# I2C_Breakout_Block.net
KiCad netlist of a schematic drawn in EAGLE
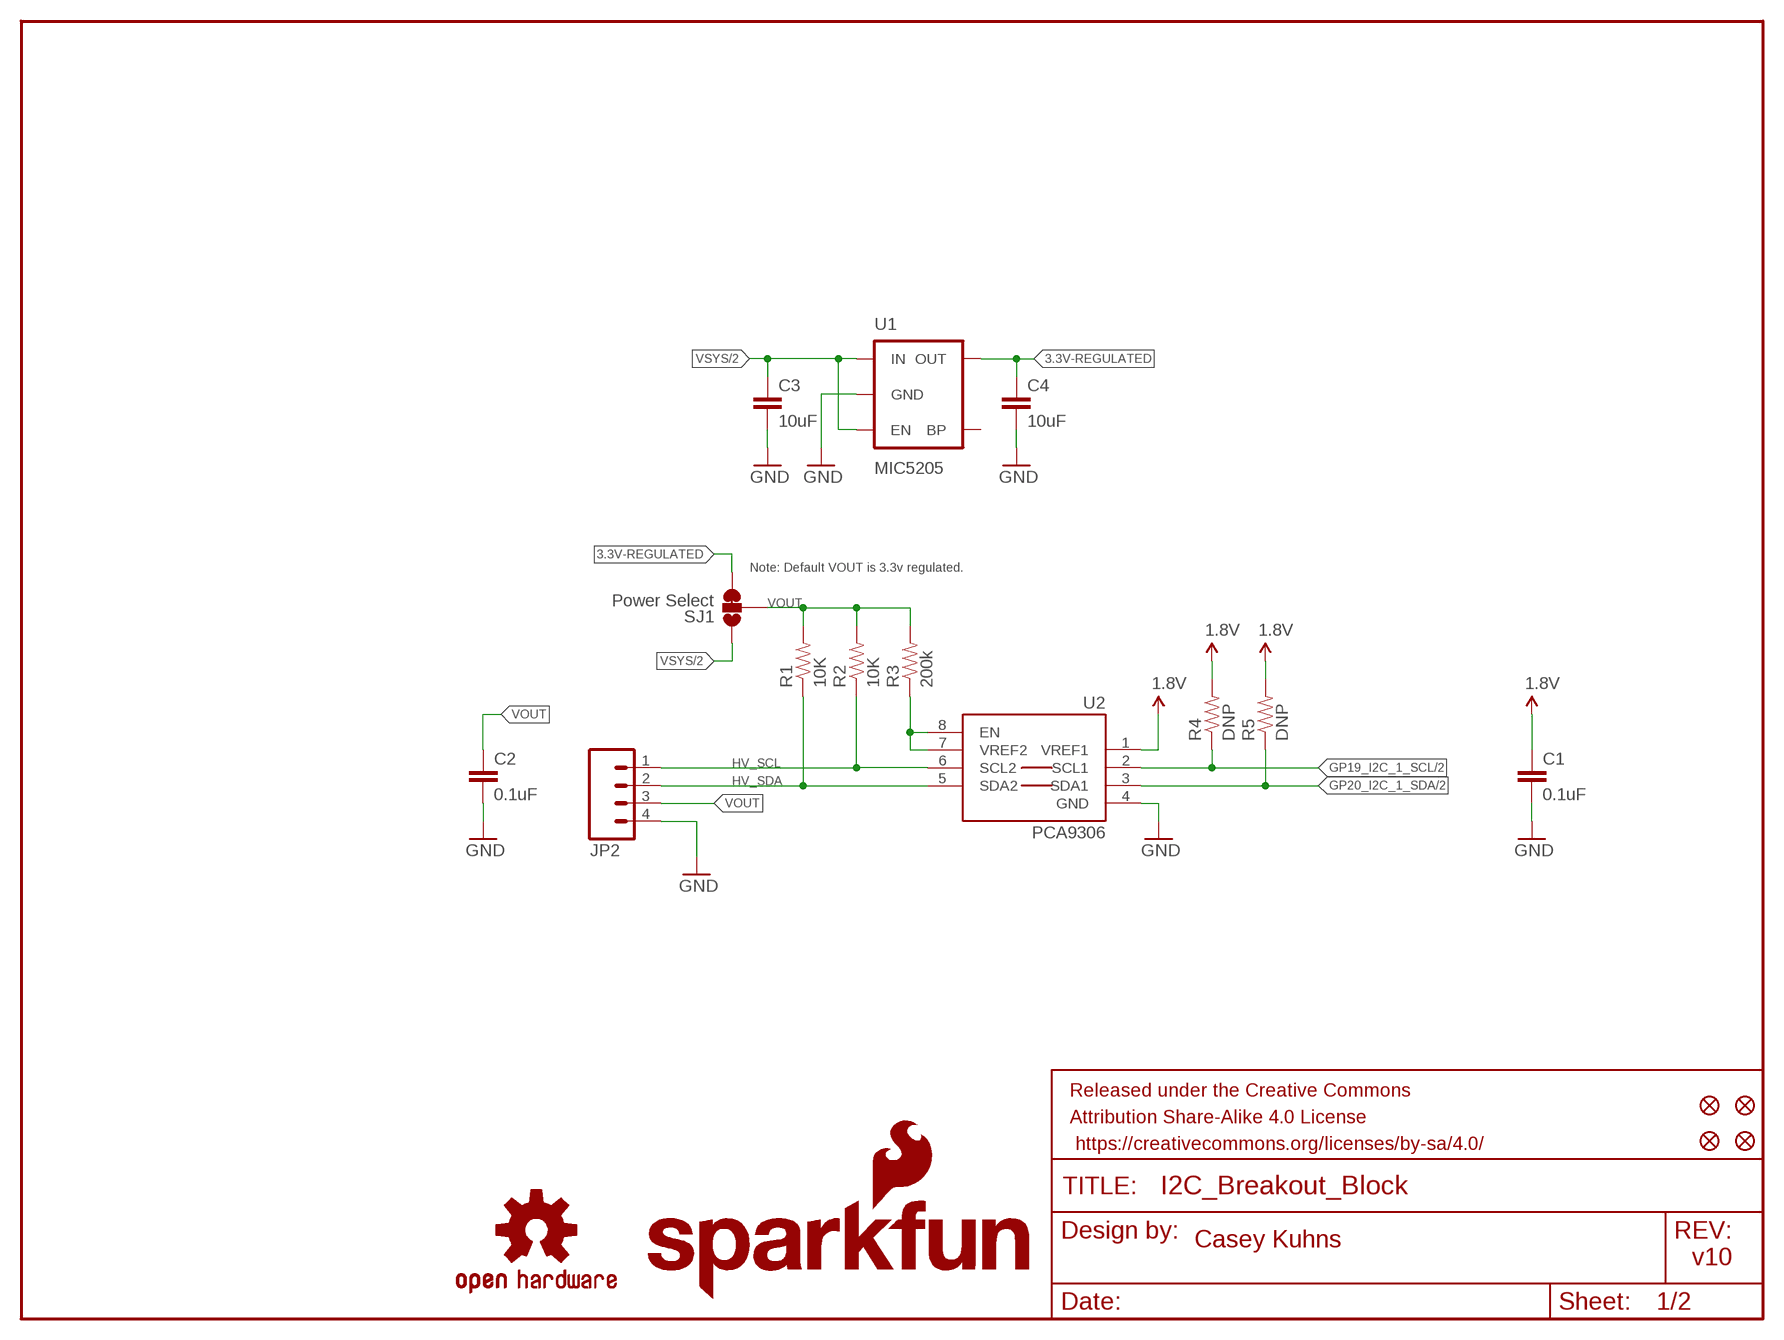
[diagram p0: schematic, sheet 1]
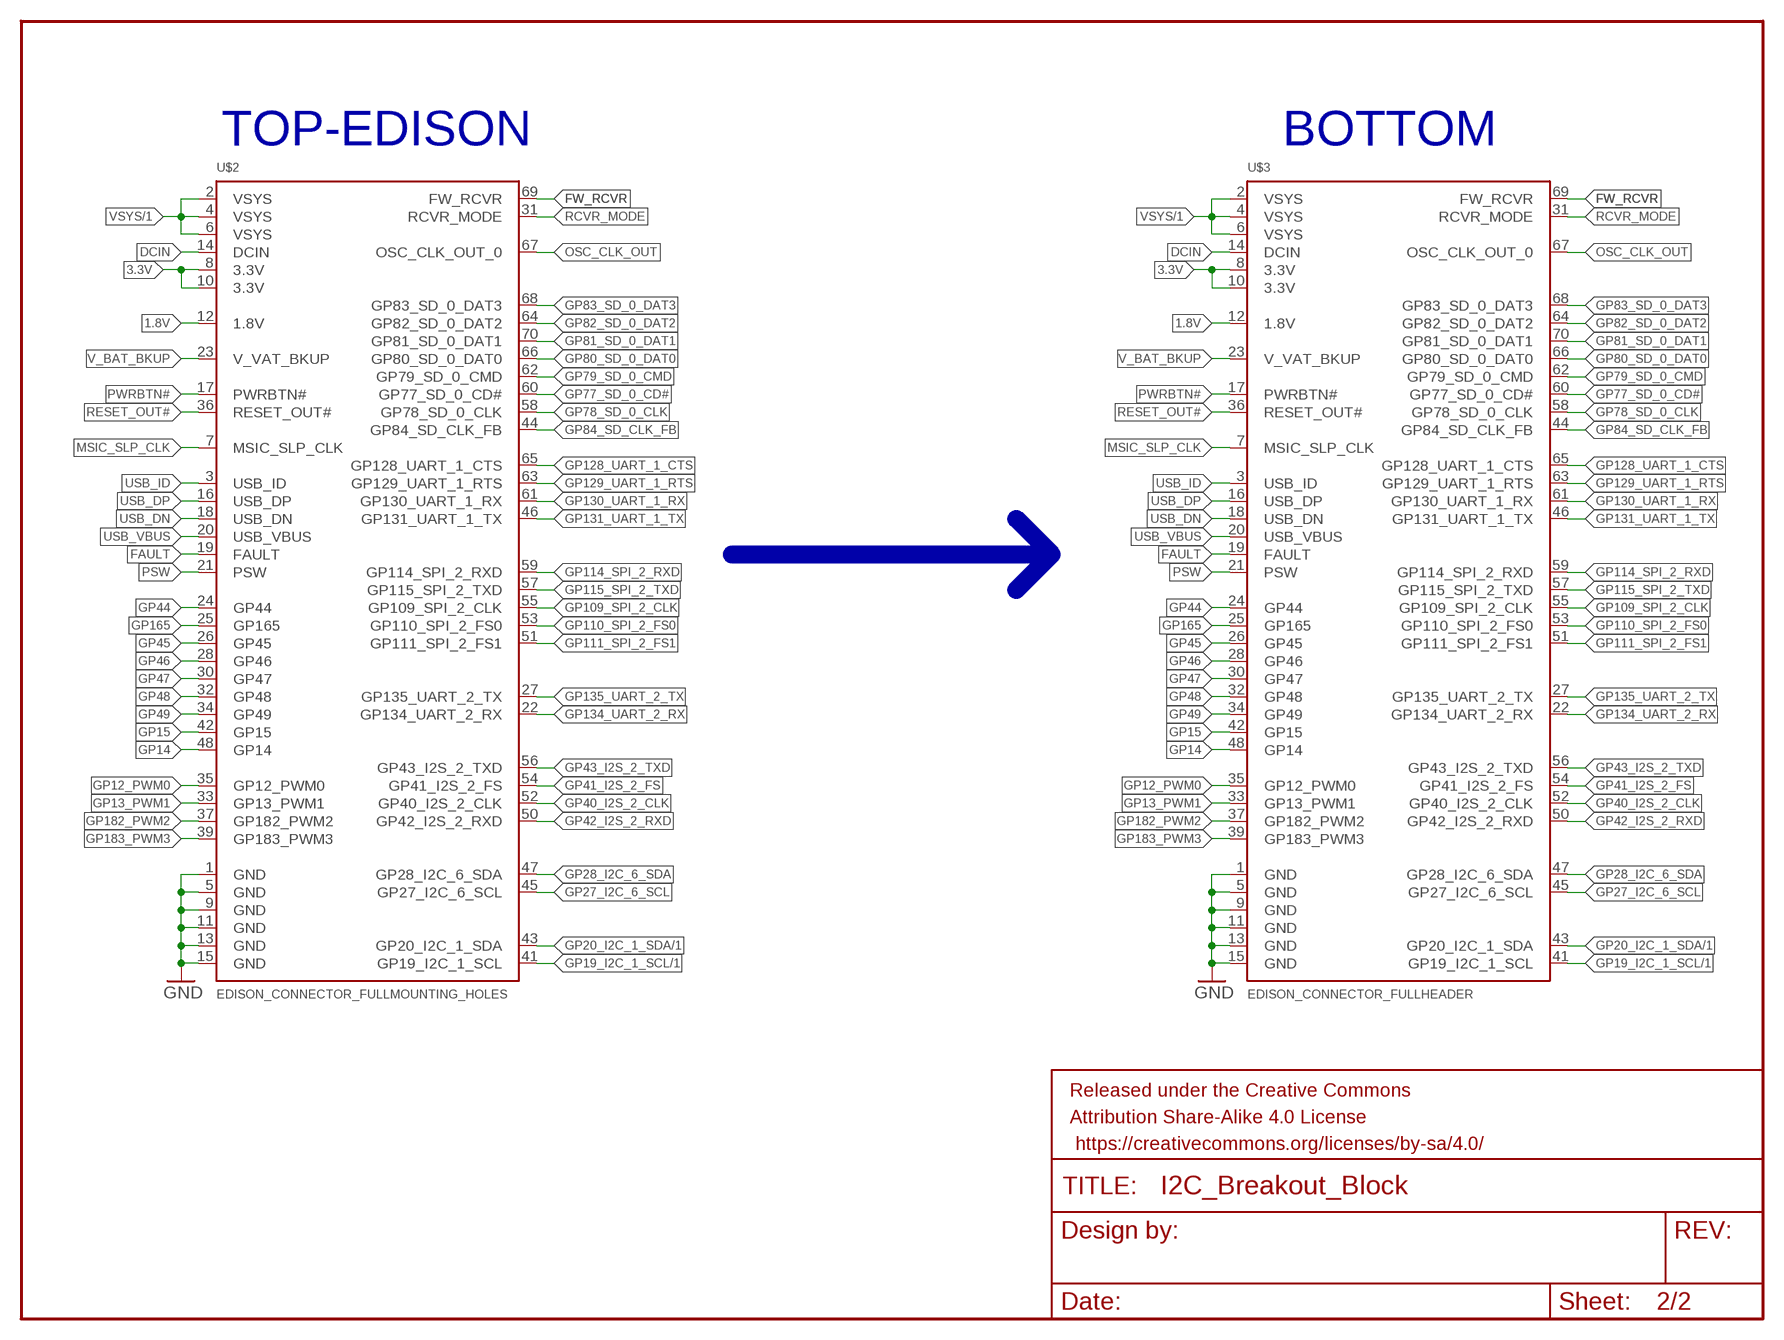
[diagram p1: schematic, sheet 2]

(export (version "E")
  (design (tool "Eeschema 10.0.6"))
  (components
    (comp (ref "FRAME2")
      (value "FRAME-LETTER")
      (footprint "eagle-import:CREATIVE_COMMONS")
      (libsource (lib "eagle-import") (part "FRAME-LETTER"))
    )
    (comp (ref "U$2")
      (value "EDISON_CONNECTOR_FULLMOUNTING_HOLES")
      (footprint "eagle-import:EDISON_DAUGHTER")
      (libsource (lib "eagle-import") (part "EDISON_CONNECTOR_FULLMOUNTING_HOLES"))
    )
    (comp (ref "U$3")
      (value "EDISON_CONNECTOR_FULLHEADER")
      (footprint "eagle-import:DF40C-70DP-0.4(51)")
      (libsource (lib "eagle-import") (part "EDISON_CONNECTOR_FULLHEADER"))
    )
    (comp (ref "C1")
      (value "0.1uF")
      (footprint "eagle-import:0603-CAP")
      (libsource (lib "eagle-import") (part "0.1UF-25V(+80/-20%)(0603)"))
    )
    (comp (ref "C2")
      (value "0.1uF")
      (footprint "eagle-import:0603-CAP")
      (libsource (lib "eagle-import") (part "0.1UF-25V(+80/-20%)(0603)"))
    )
    (comp (ref "C3")
      (value "10uF")
      (footprint "eagle-import:1206")
      (libsource (lib "eagle-import") (part "10UF-6.3V-20%(1206)"))
    )
    (comp (ref "C4")
      (value "10uF")
      (footprint "eagle-import:1206")
      (libsource (lib "eagle-import") (part "10UF-6.3V-20%(1206)"))
    )
    (comp (ref "FID1")
      (value "FIDUCIAL1X2")
      (footprint "eagle-import:FIDUCIAL-1X2")
      (libsource (lib "eagle-import") (part "FIDUCIAL1X2"))
    )
    (comp (ref "FID2")
      (value "FIDUCIAL1X2")
      (footprint "eagle-import:FIDUCIAL-1X2")
      (libsource (lib "eagle-import") (part "FIDUCIAL1X2"))
    )
    (comp (ref "FID3")
      (value "FIDUCIAL1X2")
      (footprint "eagle-import:FIDUCIAL-1X2")
      (libsource (lib "eagle-import") (part "FIDUCIAL1X2"))
    )
    (comp (ref "FID4")
      (value "FIDUCIAL1X2")
      (footprint "eagle-import:FIDUCIAL-1X2")
      (libsource (lib "eagle-import") (part "FIDUCIAL1X2"))
    )
    (comp (ref "FRAME1")
      (value "FRAME-LETTER")
      (footprint "eagle-import:CREATIVE_COMMONS")
      (libsource (lib "eagle-import") (part "FRAME-LETTER"))
    )
    (comp (ref "JP2")
      (value "M04SMD_RA_FEMALE")
      (footprint "eagle-import:1X04_SMD_RA_FEMALE")
      (libsource (lib "eagle-import") (part "M04SMD_RA_FEMALE"))
    )
    (comp (ref "LOGO1")
      (value "SFE_LOGO_NAME_FLAME.1_INCH")
      (footprint "eagle-import:SFE_LOGO_NAME_FLAME_.1")
      (libsource (lib "eagle-import") (part "SFE_LOGO_NAME_FLAME.1_INCH"))
    )
    (comp (ref "LOGO2")
      (value "OSHW-LOGOS")
      (footprint "eagle-import:OSHW-LOGO-S")
      (libsource (lib "eagle-import") (part "OSHW-LOGOS"))
    )
    (comp (ref "LOGO3")
      (value "SFE_LOGO_NAME_FLAME.1_INCH")
      (footprint "eagle-import:SFE_LOGO_NAME_FLAME_.1")
      (libsource (lib "eagle-import") (part "SFE_LOGO_NAME_FLAME.1_INCH"))
    )
    (comp (ref "LOGO4")
      (value "OSHW-LOGOS")
      (footprint "eagle-import:OSHW-LOGO-S")
      (libsource (lib "eagle-import") (part "OSHW-LOGOS"))
    )
    (comp (ref "R1")
      (value "10K")
      (footprint "eagle-import:0603-RES")
      (libsource (lib "eagle-import") (part "10KOHM1/10W1%(0603)0603"))
    )
    (comp (ref "R2")
      (value "10K")
      (footprint "eagle-import:0603-RES")
      (libsource (lib "eagle-import") (part "10KOHM1/10W1%(0603)0603"))
    )
    (comp (ref "R3")
      (value "200k")
      (footprint "eagle-import:0603-RES")
      (libsource (lib "eagle-import") (part "200KOHM1/10W1%(0603)200K"))
    )
    (comp (ref "R4")
      (value "DNP")
      (footprint "eagle-import:0603-RES")
      (libsource (lib "eagle-import") (part "2.2KOHM1/10W1%(0603)"))
    )
    (comp (ref "R5")
      (value "DNP")
      (footprint "eagle-import:0603-RES")
      (libsource (lib "eagle-import") (part "2.2KOHM1/10W1%(0603)"))
    )
    (comp (ref "SJ1")
      (value "Power Select")
      (footprint "eagle-import:PAD-JUMPER-3-2OF3_NC_BY_TRACE_YES_SILK_FULL_BOX")
      (libsource (lib "eagle-import") (part "JUMPER-PAD-3-2OF3_NC_BY_TRACE"))
    )
    (comp (ref "U1")
      (value "MIC5205")
      (footprint "eagle-import:SOT23-5")
      (libsource (lib "eagle-import") (part "MIC52053.3V"))
    )
    (comp (ref "U2")
      (value "PCA9306")
      (footprint "eagle-import:PCA9306DC-1_1")
      (libsource (lib "eagle-import") (part "PCA9306PCA9306DC-1{colon}1"))
    )
  )
  (nets
    (net (code "1") (name "1.8V") (class "Default")
      (node (ref "C1") (pin "1") (pinfunction "1_1") (pintype "passive"))
      (node (ref "R4") (pin "2") (pinfunction "2_2") (pintype "passive"))
      (node (ref "R5") (pin "2") (pinfunction "2_2") (pintype "passive"))
      (node (ref "U$2") (pin "12") (pinfunction "1.8V_12") (pintype "bidirectional"))
      (node (ref "U$3") (pin "12") (pinfunction "1.8V_12") (pintype "bidirectional"))
      (node (ref "U2") (pin "1") (pinfunction "VREF1_1") (pintype "bidirectional"))
    )
    (net (code "2") (name "3.3V") (class "Default")
      (node (ref "U$2") (pin "10") (pinfunction "3.3V_10") (pintype "bidirectional"))
      (node (ref "U$2") (pin "8") (pinfunction "3.3V_8") (pintype "bidirectional"))
      (node (ref "U$3") (pin "10") (pinfunction "3.3V_10") (pintype "bidirectional"))
      (node (ref "U$3") (pin "8") (pinfunction "3.3V_8") (pintype "bidirectional"))
    )
    (net (code "3") (name "3.3V-REGULATED") (class "Default")
      (node (ref "C4") (pin "1") (pinfunction "1_1") (pintype "passive"))
      (node (ref "SJ1") (pin "3") (pinfunction "3_3") (pintype "passive"))
      (node (ref "U1") (pin "5") (pinfunction "OUT_5") (pintype "passive"))
    )
    (net (code "4") (name "DCIN") (class "Default")
      (node (ref "U$2") (pin "14") (pinfunction "DCIN_14") (pintype "bidirectional"))
      (node (ref "U$3") (pin "14") (pinfunction "DCIN_14") (pintype "bidirectional"))
    )
    (net (code "5") (name "FAULT") (class "Default")
      (node (ref "U$2") (pin "19") (pinfunction "FAULT_19") (pintype "bidirectional"))
      (node (ref "U$3") (pin "19") (pinfunction "FAULT_19") (pintype "bidirectional"))
    )
    (net (code "6") (name "FW_RCVR") (class "Default")
      (node (ref "U$2") (pin "69") (pinfunction "FW_RCVR_69") (pintype "bidirectional"))
      (node (ref "U$3") (pin "69") (pinfunction "FW_RCVR_69") (pintype "bidirectional"))
    )
    (net (code "7") (name "GND") (class "Default")
      (node (ref "C1") (pin "2") (pinfunction "2_2") (pintype "passive"))
      (node (ref "C2") (pin "2") (pinfunction "2_2") (pintype "passive"))
      (node (ref "C3") (pin "2") (pinfunction "2_2") (pintype "passive"))
      (node (ref "C4") (pin "2") (pinfunction "2_2") (pintype "passive"))
      (node (ref "JP2") (pin "4") (pinfunction "4_4") (pintype "passive"))
      (node (ref "U$2") (pin "1") (pinfunction "GND_1") (pintype "bidirectional"))
      (node (ref "U$2") (pin "11") (pinfunction "GND_11") (pintype "bidirectional"))
      (node (ref "U$2") (pin "13") (pinfunction "GND_13") (pintype "bidirectional"))
      (node (ref "U$2") (pin "15") (pinfunction "GND_15") (pintype "bidirectional"))
      (node (ref "U$2") (pin "5") (pinfunction "GND_5") (pintype "bidirectional"))
      (node (ref "U$2") (pin "9") (pinfunction "GND_9") (pintype "bidirectional"))
      (node (ref "U$3") (pin "1") (pinfunction "GND_1") (pintype "bidirectional"))
      (node (ref "U$3") (pin "11") (pinfunction "GND_11") (pintype "bidirectional"))
      (node (ref "U$3") (pin "13") (pinfunction "GND_13") (pintype "bidirectional"))
      (node (ref "U$3") (pin "15") (pinfunction "GND_15") (pintype "bidirectional"))
      (node (ref "U$3") (pin "5") (pinfunction "GND_5") (pintype "bidirectional"))
      (node (ref "U$3") (pin "9") (pinfunction "GND_9") (pintype "bidirectional"))
      (node (ref "U1") (pin "2") (pinfunction "GND_2") (pintype "input"))
      (node (ref "U2") (pin "4") (pinfunction "GND_4") (pintype "bidirectional"))
    )
    (net (code "8") (name "GP12_PWM0") (class "Default")
      (node (ref "U$2") (pin "35") (pinfunction "GP12_PWM0_35") (pintype "bidirectional"))
      (node (ref "U$3") (pin "35") (pinfunction "GP12_PWM0_35") (pintype "bidirectional"))
    )
    (net (code "9") (name "GP13_PWM1") (class "Default")
      (node (ref "U$2") (pin "33") (pinfunction "GP13_PWM1_33") (pintype "bidirectional"))
      (node (ref "U$3") (pin "33") (pinfunction "GP13_PWM1_33") (pintype "bidirectional"))
    )
    (net (code "10") (name "GP14") (class "Default")
      (node (ref "U$2") (pin "48") (pinfunction "GP14_48") (pintype "bidirectional"))
      (node (ref "U$3") (pin "48") (pinfunction "GP14_48") (pintype "bidirectional"))
    )
    (net (code "11") (name "GP15") (class "Default")
      (node (ref "U$2") (pin "42") (pinfunction "GP15_42") (pintype "bidirectional"))
      (node (ref "U$3") (pin "42") (pinfunction "GP15_42") (pintype "bidirectional"))
    )
    (net (code "12") (name "GP19_I2C_1_SCL") (class "Default")
      (node (ref "R4") (pin "1") (pinfunction "1_1") (pintype "passive"))
      (node (ref "U$2") (pin "41") (pinfunction "GP19_I2C_1_SCL_41") (pintype "bidirectional"))
      (node (ref "U$3") (pin "41") (pinfunction "GP19_I2C_1_SCL_41") (pintype "bidirectional"))
      (node (ref "U2") (pin "2") (pinfunction "SCL1_2") (pintype "bidirectional"))
    )
    (net (code "13") (name "GP20_I2C_1_SDA") (class "Default")
      (node (ref "R5") (pin "1") (pinfunction "1_1") (pintype "passive"))
      (node (ref "U$2") (pin "43") (pinfunction "GP20_I2C_1_SDA_43") (pintype "bidirectional"))
      (node (ref "U$3") (pin "43") (pinfunction "GP20_I2C_1_SDA_43") (pintype "bidirectional"))
      (node (ref "U2") (pin "3") (pinfunction "SDA1_3") (pintype "bidirectional"))
    )
    (net (code "14") (name "GP27_I2C_6_SCL") (class "Default")
      (node (ref "U$2") (pin "45") (pinfunction "GP27_I2C_6_SCL_45") (pintype "bidirectional"))
      (node (ref "U$3") (pin "45") (pinfunction "GP27_I2C_6_SCL_45") (pintype "bidirectional"))
    )
    (net (code "15") (name "GP28_I2C_6_SDA") (class "Default")
      (node (ref "U$2") (pin "47") (pinfunction "GP28_I2C_6_SDA_47") (pintype "bidirectional"))
      (node (ref "U$3") (pin "47") (pinfunction "GP28_I2C_6_SDA_47") (pintype "bidirectional"))
    )
    (net (code "16") (name "GP40_I2S_2_CLK") (class "Default")
      (node (ref "U$2") (pin "52") (pinfunction "GP40_I2S_2_CLK_52") (pintype "bidirectional"))
      (node (ref "U$3") (pin "52") (pinfunction "GP40_I2S_2_CLK_52") (pintype "bidirectional"))
    )
    (net (code "17") (name "GP41_I2S_2_FS") (class "Default")
      (node (ref "U$2") (pin "54") (pinfunction "GP41_I2S_2_FS_54") (pintype "bidirectional"))
      (node (ref "U$3") (pin "54") (pinfunction "GP41_I2S_2_FS_54") (pintype "bidirectional"))
    )
    (net (code "18") (name "GP42_I2S_2_RXD") (class "Default")
      (node (ref "U$2") (pin "50") (pinfunction "GP42_I2S_2_RXD_50") (pintype "bidirectional"))
      (node (ref "U$3") (pin "50") (pinfunction "GP42_I2S_2_RXD_50") (pintype "bidirectional"))
    )
    (net (code "19") (name "GP43_I2S_2_TXD") (class "Default")
      (node (ref "U$2") (pin "56") (pinfunction "GP43_I2S_2_TXD_56") (pintype "bidirectional"))
      (node (ref "U$3") (pin "56") (pinfunction "GP43_I2S_2_TXD_56") (pintype "bidirectional"))
    )
    (net (code "20") (name "GP44") (class "Default")
      (node (ref "U$2") (pin "24") (pinfunction "GP44_24") (pintype "bidirectional"))
      (node (ref "U$3") (pin "24") (pinfunction "GP44_24") (pintype "bidirectional"))
    )
    (net (code "21") (name "GP45") (class "Default")
      (node (ref "U$2") (pin "26") (pinfunction "GP45_26") (pintype "bidirectional"))
      (node (ref "U$3") (pin "26") (pinfunction "GP45_26") (pintype "bidirectional"))
    )
    (net (code "22") (name "GP46") (class "Default")
      (node (ref "U$2") (pin "28") (pinfunction "GP46_28") (pintype "bidirectional"))
      (node (ref "U$3") (pin "28") (pinfunction "GP46_28") (pintype "bidirectional"))
    )
    (net (code "23") (name "GP47") (class "Default")
      (node (ref "U$2") (pin "30") (pinfunction "GP47_30") (pintype "bidirectional"))
      (node (ref "U$3") (pin "30") (pinfunction "GP47_30") (pintype "bidirectional"))
    )
    (net (code "24") (name "GP48") (class "Default")
      (node (ref "U$2") (pin "32") (pinfunction "GP48_32") (pintype "bidirectional"))
      (node (ref "U$3") (pin "32") (pinfunction "GP48_32") (pintype "bidirectional"))
    )
    (net (code "25") (name "GP49") (class "Default")
      (node (ref "U$2") (pin "34") (pinfunction "GP49_34") (pintype "bidirectional"))
      (node (ref "U$3") (pin "34") (pinfunction "GP49_34") (pintype "bidirectional"))
    )
    (net (code "26") (name "GP77_SD_0_CD#") (class "Default")
      (node (ref "U$2") (pin "60") (pinfunction "GP77_SD_0_CD#_60") (pintype "bidirectional"))
      (node (ref "U$3") (pin "60") (pinfunction "GP77_SD_0_CD#_60") (pintype "bidirectional"))
    )
    (net (code "27") (name "GP78_SD_0_CLK") (class "Default")
      (node (ref "U$2") (pin "58") (pinfunction "GP78_SD_0_CLK_58") (pintype "bidirectional"))
      (node (ref "U$3") (pin "58") (pinfunction "GP78_SD_0_CLK_58") (pintype "bidirectional"))
    )
    (net (code "28") (name "GP79_SD_0_CMD") (class "Default")
      (node (ref "U$2") (pin "62") (pinfunction "GP79_SD_0_CMD_62") (pintype "bidirectional"))
      (node (ref "U$3") (pin "62") (pinfunction "GP79_SD_0_CMD_62") (pintype "bidirectional"))
    )
    (net (code "29") (name "GP80_SD_0_DAT0") (class "Default")
      (node (ref "U$2") (pin "66") (pinfunction "GP80_SD_0_DAT0_66") (pintype "bidirectional"))
      (node (ref "U$3") (pin "66") (pinfunction "GP80_SD_0_DAT0_66") (pintype "bidirectional"))
    )
    (net (code "30") (name "GP81_SD_0_DAT1") (class "Default")
      (node (ref "U$2") (pin "70") (pinfunction "GP81_SD_0_DAT1_70") (pintype "bidirectional"))
      (node (ref "U$3") (pin "70") (pinfunction "GP81_SD_0_DAT1_70") (pintype "bidirectional"))
    )
    (net (code "31") (name "GP82_SD_0_DAT2") (class "Default")
      (node (ref "U$2") (pin "64") (pinfunction "GP82_SD_0_DAT2_64") (pintype "bidirectional"))
      (node (ref "U$3") (pin "64") (pinfunction "GP82_SD_0_DAT2_64") (pintype "bidirectional"))
    )
    (net (code "32") (name "GP83_SD_0_DAT3") (class "Default")
      (node (ref "U$2") (pin "68") (pinfunction "GP83_SD_0_DAT3_68") (pintype "bidirectional"))
      (node (ref "U$3") (pin "68") (pinfunction "GP83_SD_0_DAT3_68") (pintype "bidirectional"))
    )
    (net (code "33") (name "GP84_SD_CLK_FB") (class "Default")
      (node (ref "U$2") (pin "44") (pinfunction "GP84_SD_CLK_FB_44") (pintype "bidirectional"))
      (node (ref "U$3") (pin "44") (pinfunction "GP84_SD_CLK_FB_44") (pintype "bidirectional"))
    )
    (net (code "34") (name "GP109_SPI_2_CLK") (class "Default")
      (node (ref "U$2") (pin "55") (pinfunction "GP109_SPI_2_CLK_55") (pintype "bidirectional"))
      (node (ref "U$3") (pin "55") (pinfunction "GP109_SPI_2_CLK_55") (pintype "bidirectional"))
    )
    (net (code "35") (name "GP110_SPI_2_FS0") (class "Default")
      (node (ref "U$2") (pin "53") (pinfunction "GP110_SPI_2_FS0_53") (pintype "bidirectional"))
      (node (ref "U$3") (pin "53") (pinfunction "GP110_SPI_2_FS0_53") (pintype "bidirectional"))
    )
    (net (code "36") (name "GP111_SPI_2_FS1") (class "Default")
      (node (ref "U$2") (pin "51") (pinfunction "GP111_SPI_2_FS1_51") (pintype "bidirectional"))
      (node (ref "U$3") (pin "51") (pinfunction "GP111_SPI_2_FS1_51") (pintype "bidirectional"))
    )
    (net (code "37") (name "GP114_SPI_2_RXD") (class "Default")
      (node (ref "U$2") (pin "59") (pinfunction "GP114_SPI_2_RXD_59") (pintype "bidirectional"))
      (node (ref "U$3") (pin "59") (pinfunction "GP114_SPI_2_RXD_59") (pintype "bidirectional"))
    )
    (net (code "38") (name "GP115_SPI_2_TXD") (class "Default")
      (node (ref "U$2") (pin "57") (pinfunction "GP115_SPI_2_TXD_57") (pintype "bidirectional"))
      (node (ref "U$3") (pin "57") (pinfunction "GP115_SPI_2_TXD_57") (pintype "bidirectional"))
    )
    (net (code "39") (name "GP128_UART_1_CTS") (class "Default")
      (node (ref "U$2") (pin "65") (pinfunction "GP128_UART_1_CTS_65") (pintype "bidirectional"))
      (node (ref "U$3") (pin "65") (pinfunction "GP128_UART_1_CTS_65") (pintype "bidirectional"))
    )
    (net (code "40") (name "GP129_UART_1_RTS") (class "Default")
      (node (ref "U$2") (pin "63") (pinfunction "GP129_UART_1_RTS_63") (pintype "bidirectional"))
      (node (ref "U$3") (pin "63") (pinfunction "GP129_UART_1_RTS_63") (pintype "bidirectional"))
    )
    (net (code "41") (name "GP130_UART_1_RX") (class "Default")
      (node (ref "U$2") (pin "61") (pinfunction "GP130_UART_1_RX_61") (pintype "bidirectional"))
      (node (ref "U$3") (pin "61") (pinfunction "GP130_UART_1_RX_61") (pintype "bidirectional"))
    )
    (net (code "42") (name "GP131_UART_1_TX") (class "Default")
      (node (ref "U$2") (pin "46") (pinfunction "GP131_UART_1_TX_46") (pintype "bidirectional"))
      (node (ref "U$3") (pin "46") (pinfunction "GP131_UART_1_TX_46") (pintype "bidirectional"))
    )
    (net (code "43") (name "GP134_UART_2_RX") (class "Default")
      (node (ref "U$2") (pin "22") (pinfunction "GP134_UART_2_RX_22") (pintype "bidirectional"))
      (node (ref "U$3") (pin "22") (pinfunction "GP134_UART_2_RX_22") (pintype "bidirectional"))
    )
    (net (code "44") (name "GP135_UART_2_TX") (class "Default")
      (node (ref "U$2") (pin "27") (pinfunction "GP135_UART_2_TX_27") (pintype "bidirectional"))
      (node (ref "U$3") (pin "27") (pinfunction "GP135_UART_2_TX_27") (pintype "bidirectional"))
    )
    (net (code "45") (name "GP165") (class "Default")
      (node (ref "U$2") (pin "25") (pinfunction "GP165_25") (pintype "bidirectional"))
      (node (ref "U$3") (pin "25") (pinfunction "GP165_25") (pintype "bidirectional"))
    )
    (net (code "46") (name "GP182_PWM2") (class "Default")
      (node (ref "U$2") (pin "37") (pinfunction "GP182_PWM2_37") (pintype "bidirectional"))
      (node (ref "U$3") (pin "37") (pinfunction "GP182_PWM2_37") (pintype "bidirectional"))
    )
    (net (code "47") (name "GP183_PWM3") (class "Default")
      (node (ref "U$2") (pin "39") (pinfunction "GP183_PWM3_39") (pintype "bidirectional"))
      (node (ref "U$3") (pin "39") (pinfunction "GP183_PWM3_39") (pintype "bidirectional"))
    )
    (net (code "48") (name "HV_SCL") (class "Default")
      (node (ref "JP2") (pin "1") (pinfunction "1_1") (pintype "passive"))
      (node (ref "R2") (pin "1") (pinfunction "1_1") (pintype "passive"))
      (node (ref "U2") (pin "6") (pinfunction "SCL2_6") (pintype "bidirectional"))
    )
    (net (code "49") (name "HV_SDA") (class "Default")
      (node (ref "JP2") (pin "2") (pinfunction "2_2") (pintype "passive"))
      (node (ref "R1") (pin "1") (pinfunction "1_1") (pintype "passive"))
      (node (ref "U2") (pin "5") (pinfunction "SDA2_5") (pintype "bidirectional"))
    )
    (net (code "50") (name "MSIC_SLP_CLK") (class "Default")
      (node (ref "U$2") (pin "7") (pinfunction "MSIC_SLP_CLK_7") (pintype "bidirectional"))
      (node (ref "U$3") (pin "7") (pinfunction "MSIC_SLP_CLK_7") (pintype "bidirectional"))
    )
    (net (code "51") (name "Net-(U2-EN)") (class "Default")
      (node (ref "R3") (pin "1") (pinfunction "1_1") (pintype "passive"))
      (node (ref "U2") (pin "7") (pinfunction "VREF2_7") (pintype "bidirectional"))
      (node (ref "U2") (pin "8") (pinfunction "EN_8") (pintype "bidirectional"))
    )
    (net (code "52") (name "OSC_CLK_OUT") (class "Default")
      (node (ref "U$2") (pin "67") (pinfunction "OSC_CLK_OUT_0_67") (pintype "bidirectional"))
      (node (ref "U$3") (pin "67") (pinfunction "OSC_CLK_OUT_0_67") (pintype "bidirectional"))
    )
    (net (code "53") (name "PSW") (class "Default")
      (node (ref "U$2") (pin "21") (pinfunction "PSW_21") (pintype "bidirectional"))
      (node (ref "U$3") (pin "21") (pinfunction "PSW_21") (pintype "bidirectional"))
    )
    (net (code "54") (name "PWRBTN#") (class "Default")
      (node (ref "U$2") (pin "17") (pinfunction "PWRBTN#_17") (pintype "bidirectional"))
      (node (ref "U$3") (pin "17") (pinfunction "PWRBTN#_17") (pintype "bidirectional"))
    )
    (net (code "55") (name "RCVR_MODE") (class "Default")
      (node (ref "U$2") (pin "31") (pinfunction "RCVR_MODE_31") (pintype "bidirectional"))
      (node (ref "U$3") (pin "31") (pinfunction "RCVR_MODE_31") (pintype "bidirectional"))
    )
    (net (code "56") (name "RESET_OUT#") (class "Default")
      (node (ref "U$2") (pin "36") (pinfunction "RESET_OUT#_36") (pintype "bidirectional"))
      (node (ref "U$3") (pin "36") (pinfunction "RESET_OUT#_36") (pintype "bidirectional"))
    )
    (net (code "57") (name "USB_DN") (class "Default")
      (node (ref "U$2") (pin "18") (pinfunction "USB_DN_18") (pintype "bidirectional"))
      (node (ref "U$3") (pin "18") (pinfunction "USB_DN_18") (pintype "bidirectional"))
    )
    (net (code "58") (name "USB_DP") (class "Default")
      (node (ref "U$2") (pin "16") (pinfunction "USB_DP_16") (pintype "bidirectional"))
      (node (ref "U$3") (pin "16") (pinfunction "USB_DP_16") (pintype "bidirectional"))
    )
    (net (code "59") (name "USB_ID") (class "Default")
      (node (ref "U$2") (pin "3") (pinfunction "USB_ID_3") (pintype "bidirectional"))
      (node (ref "U$3") (pin "3") (pinfunction "USB_ID_3") (pintype "bidirectional"))
    )
    (net (code "60") (name "USB_VBUS") (class "Default")
      (node (ref "U$2") (pin "20") (pinfunction "USB_VBUS_20") (pintype "bidirectional"))
      (node (ref "U$3") (pin "20") (pinfunction "USB_VBUS_20") (pintype "bidirectional"))
    )
    (net (code "61") (name "VOUT") (class "Default")
      (node (ref "C2") (pin "1") (pinfunction "1_1") (pintype "passive"))
      (node (ref "JP2") (pin "3") (pinfunction "3_3") (pintype "passive"))
      (node (ref "R1") (pin "2") (pinfunction "2_2") (pintype "passive"))
      (node (ref "R2") (pin "2") (pinfunction "2_2") (pintype "passive"))
      (node (ref "R3") (pin "2") (pinfunction "2_2") (pintype "passive"))
      (node (ref "SJ1") (pin "2") (pinfunction "2_2") (pintype "passive"))
    )
    (net (code "62") (name "VSYS") (class "Default")
      (node (ref "C3") (pin "1") (pinfunction "1_1") (pintype "passive"))
      (node (ref "SJ1") (pin "1") (pinfunction "1_1") (pintype "passive"))
      (node (ref "U$2") (pin "2") (pinfunction "VSYS_2") (pintype "bidirectional"))
      (node (ref "U$2") (pin "4") (pinfunction "VSYS_4") (pintype "bidirectional"))
      (node (ref "U$2") (pin "6") (pinfunction "VSYS_6") (pintype "bidirectional"))
      (node (ref "U$3") (pin "2") (pinfunction "VSYS_2") (pintype "bidirectional"))
      (node (ref "U$3") (pin "4") (pinfunction "VSYS_4") (pintype "bidirectional"))
      (node (ref "U$3") (pin "6") (pinfunction "VSYS_6") (pintype "bidirectional"))
      (node (ref "U1") (pin "1") (pinfunction "IN_1") (pintype "input"))
      (node (ref "U1") (pin "3") (pinfunction "EN_3") (pintype "input"))
    )
    (net (code "63") (name "V_BAT_BKUP") (class "Default")
      (node (ref "U$2") (pin "23") (pinfunction "V_VAT_BKUP_23") (pintype "bidirectional"))
      (node (ref "U$3") (pin "23") (pinfunction "V_VAT_BKUP_23") (pintype "bidirectional"))
    )
    (net (code "64") (name "unconnected-(U1-BP-Pad4)") (class "Default")
      (node (ref "U1") (pin "4") (pinfunction "BP_4") (pintype "input"))
    )
  )
)
